# grid-rfduino.net
KiCad netlist of a schematic drawn in EAGLE
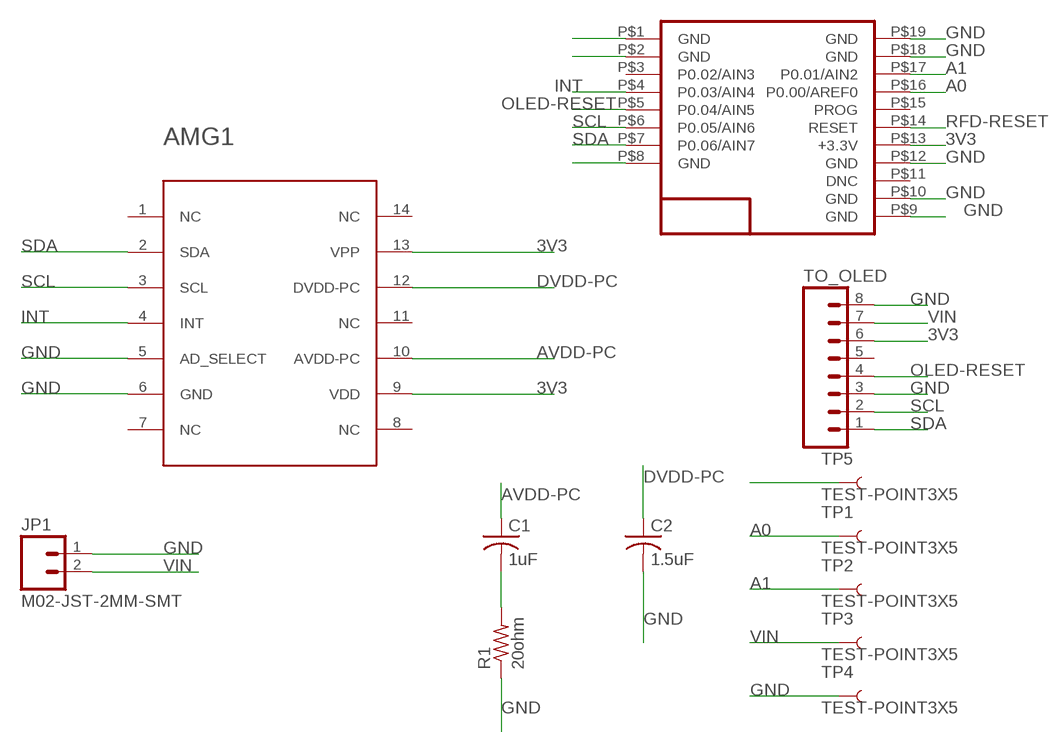
[diagram p0: schematic, sheet 1]

(export (version "E")
  (design (tool "Eeschema 10.0.6"))
  (components
    (comp (ref "AMG1")
      (value "AMG8831")
      (footprint "eagle-import:AMG8831")
      (libsource (lib "eagle-import") (part "AMG8831"))
    )
    (comp (ref "C1")
      (value "1uF")
      (footprint "eagle-import:C0805")
      (libsource (lib "eagle-import") (part "C-USC0805"))
    )
    (comp (ref "C2")
      (value "1.5uF")
      (footprint "eagle-import:C0805")
      (libsource (lib "eagle-import") (part "C-USC0805"))
    )
    (comp (ref "JP1")
      (value "M02-JST-2MM-SMT")
      (footprint "eagle-import:JST-2-SMD")
      (libsource (lib "eagle-import") (part "M02-JST-2MM-SMT"))
    )
    (comp (ref "R1")
      (value "20ohm")
      (footprint "eagle-import:M0805")
      (libsource (lib "eagle-import") (part "R-US_M0805"))
    )
    (comp (ref "TO_OLED")
      (value "M08LOCK")
      (footprint "eagle-import:1X08_LOCK")
      (libsource (lib "eagle-import") (part "M08LOCK"))
    )
    (comp (ref "TP1")
      (value "TEST-POINT3X5")
      (footprint "eagle-import:PAD.03X.05")
      (libsource (lib "eagle-import") (part "TEST-POINT3X5"))
    )
    (comp (ref "TP2")
      (value "TEST-POINT3X5")
      (footprint "eagle-import:PAD.03X.05")
      (libsource (lib "eagle-import") (part "TEST-POINT3X5"))
    )
    (comp (ref "TP3")
      (value "TEST-POINT3X5")
      (footprint "eagle-import:PAD.03X.05")
      (libsource (lib "eagle-import") (part "TEST-POINT3X5"))
    )
    (comp (ref "TP4")
      (value "TEST-POINT3X5")
      (footprint "eagle-import:PAD.03X.05")
      (libsource (lib "eagle-import") (part "TEST-POINT3X5"))
    )
    (comp (ref "TP5")
      (value "TEST-POINT3X5")
      (footprint "eagle-import:PAD.03X.05")
      (libsource (lib "eagle-import") (part "TEST-POINT3X5"))
    )
    (comp (ref "U$1")
      (value "RFD22301")
      (footprint "eagle-import:RFD21733")
      (libsource (lib "eagle-import") (part "RFD22301"))
    )
  )
  (nets
    (net (code "1") (name "/3V3") (class "Default")
      (node (ref "AMG1") (pin "13") (pinfunction "VPP_13") (pintype "power_in"))
      (node (ref "AMG1") (pin "9") (pinfunction "VDD_9") (pintype "power_in"))
      (node (ref "TO_OLED") (pin "6") (pinfunction "6_6") (pintype "passive"))
      (node (ref "U$1") (pin "P$13") (pinfunction "+3.3V_P$13") (pintype "bidirectional"))
    )
    (net (code "2") (name "/A0") (class "Default")
      (node (ref "TP1") (pin "P$1") (pinfunction "1_P$1") (pintype "bidirectional"))
      (node (ref "U$1") (pin "P$16") (pinfunction "P0.00/AREF0_P$16") (pintype "bidirectional"))
    )
    (net (code "3") (name "/A1") (class "Default")
      (node (ref "TP2") (pin "P$1") (pinfunction "1_P$1") (pintype "bidirectional"))
      (node (ref "U$1") (pin "P$17") (pinfunction "P0.01/AIN2_P$17") (pintype "bidirectional"))
    )
    (net (code "4") (name "/AVDD-PC") (class "Default")
      (node (ref "AMG1") (pin "10") (pinfunction "AVDD-PC_10") (pintype "power_in"))
      (node (ref "C1") (pin "1") (pinfunction "1_1") (pintype "passive"))
    )
    (net (code "5") (name "/DVDD-PC") (class "Default")
      (node (ref "AMG1") (pin "12") (pinfunction "DVDD-PC_12") (pintype "power_in"))
      (node (ref "C2") (pin "1") (pinfunction "1_1") (pintype "passive"))
    )
    (net (code "6") (name "/GND") (class "Default")
      (node (ref "AMG1") (pin "5") (pinfunction "AD_SELECT_5") (pintype "bidirectional"))
      (node (ref "AMG1") (pin "6") (pinfunction "GND_6") (pintype "power_in"))
      (node (ref "C2") (pin "2") (pinfunction "2_2") (pintype "passive"))
      (node (ref "JP1") (pin "1") (pinfunction "2_1") (pintype "passive"))
      (node (ref "R1") (pin "1") (pinfunction "1_1") (pintype "passive"))
      (node (ref "TO_OLED") (pin "3") (pinfunction "3_3") (pintype "passive"))
      (node (ref "TO_OLED") (pin "8") (pinfunction "8_8") (pintype "passive"))
      (node (ref "TP4") (pin "P$1") (pinfunction "1_P$1") (pintype "bidirectional"))
      (node (ref "U$1") (pin "P$1") (pinfunction "GND_P$1") (pintype "bidirectional"))
      (node (ref "U$1") (pin "P$10") (pinfunction "GND_P$10") (pintype "bidirectional"))
      (node (ref "U$1") (pin "P$12") (pinfunction "GND_P$12") (pintype "bidirectional"))
      (node (ref "U$1") (pin "P$18") (pinfunction "GND_P$18") (pintype "bidirectional"))
      (node (ref "U$1") (pin "P$19") (pinfunction "GND_P$19") (pintype "bidirectional"))
      (node (ref "U$1") (pin "P$2") (pinfunction "GND_P$2") (pintype "bidirectional"))
      (node (ref "U$1") (pin "P$8") (pinfunction "GND_P$8") (pintype "bidirectional"))
      (node (ref "U$1") (pin "P$9") (pinfunction "GND_P$9") (pintype "bidirectional"))
    )
    (net (code "7") (name "/INT") (class "Default")
      (node (ref "AMG1") (pin "4") (pinfunction "INT_4") (pintype "bidirectional"))
      (node (ref "U$1") (pin "P$4") (pinfunction "P0.03/AIN4_P$4") (pintype "bidirectional"))
    )
    (net (code "8") (name "/OLED-RESET") (class "Default")
      (node (ref "TO_OLED") (pin "4") (pinfunction "4_4") (pintype "passive"))
      (node (ref "U$1") (pin "P$5") (pinfunction "P0.04/AIN5_P$5") (pintype "bidirectional"))
    )
    (net (code "9") (name "/RFD-RESET") (class "Default")
      (node (ref "TP5") (pin "P$1") (pinfunction "1_P$1") (pintype "bidirectional"))
      (node (ref "U$1") (pin "P$14") (pinfunction "RESET_P$14") (pintype "bidirectional"))
    )
    (net (code "10") (name "/SCL") (class "Default")
      (node (ref "AMG1") (pin "3") (pinfunction "SCL_3") (pintype "bidirectional"))
      (node (ref "TO_OLED") (pin "2") (pinfunction "2_2") (pintype "passive"))
      (node (ref "U$1") (pin "P$6") (pinfunction "P0.05/AIN6_P$6") (pintype "bidirectional"))
    )
    (net (code "11") (name "/SDA") (class "Default")
      (node (ref "AMG1") (pin "2") (pinfunction "SDA_2") (pintype "bidirectional"))
      (node (ref "TO_OLED") (pin "1") (pinfunction "1_1") (pintype "passive"))
      (node (ref "U$1") (pin "P$7") (pinfunction "P0.06/AIN7_P$7") (pintype "bidirectional"))
    )
    (net (code "12") (name "/VIN") (class "Default")
      (node (ref "JP1") (pin "2") (pinfunction "1_2") (pintype "passive"))
      (node (ref "TO_OLED") (pin "7") (pinfunction "7_7") (pintype "passive"))
      (node (ref "TP3") (pin "P$1") (pinfunction "1_P$1") (pintype "bidirectional"))
    )
    (net (code "13") (name "Net-(C1-Pad2)") (class "Default")
      (node (ref "C1") (pin "2") (pinfunction "2_2") (pintype "passive"))
      (node (ref "R1") (pin "2") (pinfunction "2_2") (pintype "passive"))
    )
    (net (code "14") (name "unconnected-(AMG1-NC-Pad1)") (class "Default")
      (node (ref "AMG1") (pin "1") (pinfunction "NC_1") (pintype "no_connect"))
    )
    (net (code "15") (name "unconnected-(AMG1-NC-Pad7)") (class "Default")
      (node (ref "AMG1") (pin "7") (pinfunction "NC_7") (pintype "no_connect"))
    )
    (net (code "16") (name "unconnected-(AMG1-NC-Pad8)") (class "Default")
      (node (ref "AMG1") (pin "8") (pinfunction "NC_8") (pintype "no_connect"))
    )
    (net (code "17") (name "unconnected-(AMG1-NC-Pad11)") (class "Default")
      (node (ref "AMG1") (pin "11") (pinfunction "NC_11") (pintype "no_connect"))
    )
    (net (code "18") (name "unconnected-(AMG1-NC-Pad14)") (class "Default")
      (node (ref "AMG1") (pin "14") (pinfunction "NC_14") (pintype "no_connect"))
    )
    (net (code "19") (name "unconnected-(TO_OLED-Pad5)") (class "Default")
      (node (ref "TO_OLED") (pin "5") (pinfunction "5_5") (pintype "passive"))
    )
    (net (code "20") (name "unconnected-(U$1-DNC-PadP$11)") (class "Default")
      (node (ref "U$1") (pin "P$11") (pinfunction "DNC_P$11") (pintype "bidirectional"))
    )
    (net (code "21") (name "unconnected-(U$1-P0.02{slash}AIN3-PadP$3)") (class "Default")
      (node (ref "U$1") (pin "P$3") (pinfunction "P0.02/AIN3_P$3") (pintype "bidirectional"))
    )
    (net (code "22") (name "unconnected-(U$1-PROG-PadP$15)") (class "Default")
      (node (ref "U$1") (pin "P$15") (pinfunction "PROG_P$15") (pintype "bidirectional"))
    )
  )
)
